# ESP32_PCB.net
KiCad netlist of a schematic drawn in Altium Designer
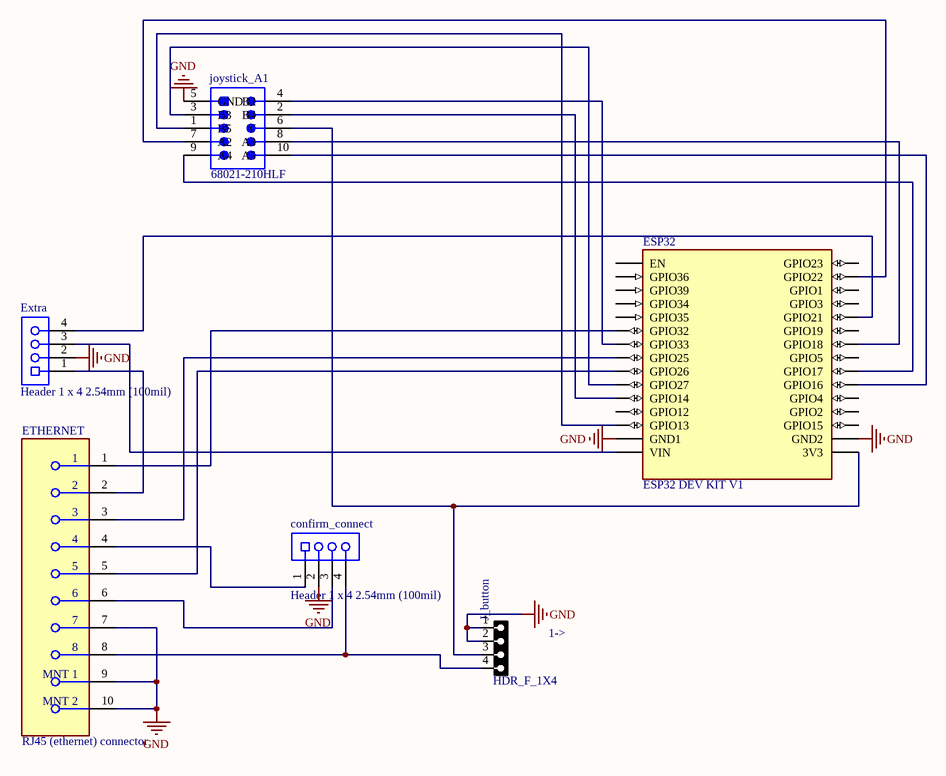
[diagram p0: ESP32_PCB.SchDoc]

(export (version "E")
  (design (tool "Eeschema 10.0.6"))
  (components
    (comp (ref "confirm_connect")
      (value "Header 1 x 4 2.54mm (100mil)")
      (footprint "New footprint 1")
      (libsource (lib "Reykjavik University") (part "New symbol 1"))
    )
    (comp (ref "ESP32")
      (value "ESP32 DEV KIT V1")
      (footprint "ESP32-DEV-KIT-V1")
      (description "ESP-WROOM-32 https://www.aliexpress.com/item/1005006771532302.html")
      (fields (field (name "MP") "ESP-WROOM-32") (field (name "MF") "Espressif Systems"))
      (libsource (lib "Reykjavik University") (part "ESP-WROOM-32"))
    )
    (comp (ref "ETHERNET")
      (value "RJ45 (ethernet) connector")
      (footprint "FP-1-406541-1-MFG")
      (description "Modular Connector, RJ45 Jack, 1 x 1 (Port), 8P8C, Cat5, Through Hole Mount")
      (libsource (lib "Reykjavik University") (part "d6c685936813e271102b42d67b1ef4a"))
    )
    (comp (ref "Extra")
      (value "Header 1 x 4 2.54mm (100mil)")
      (footprint "New footprint 1")
      (libsource (lib "") (part "New symbol 1_1"))
    )
    (comp (ref "joystick_A1")
      (value "68021-210HLF")
      (footprint "FCI-68021-210HLF-10_V")
      (description "Male Header, Pitch 2.54 mm, 2 x 5 Position, Height 4.83 mm, Tail Length 3.05 mm, Bulk")
      (fields (field (name "MANUFACTURER") "FCI Electronics"))
      (libsource (lib "Reykjavik University") (part "CN-2P-M-R10"))
    )
    (comp (ref "J_button")
      (value "HDR_F_1X4")
      (footprint "HDR_F_1X4")
      (description "Female header 1x4 2.54mm pitch")
      (libsource (lib "Reykjavik University") (part "HDRLP_F_1X4"))
    )
  )
  (nets
    (net (code "1") (name "GND") (class "Default")
      (node (ref "ESP32") (pin "J1_14") (pinfunction "GND1_J1_14") (pintype "power_in"))
      (node (ref "ESP32") (pin "J3_14") (pinfunction "GND2_J3_14") (pintype "power_in"))
      (node (ref "ETHERNET") (pin "10") (pinfunction "MNT_2_10") (pintype "passive"))
      (node (ref "ETHERNET") (pin "7") (pinfunction "7_7") (pintype "passive"))
      (node (ref "ETHERNET") (pin "9") (pinfunction "MNT_1_9") (pintype "passive"))
      (node (ref "Extra") (pin "2") (pinfunction "2_2") (pintype "passive"))
      (node (ref "J_button") (pin "1") (pinfunction "1_1") (pintype "passive"))
      (node (ref "J_button") (pin "2") (pinfunction "2_2") (pintype "passive"))
      (node (ref "confirm_connect") (pin "2") (pinfunction "2_2") (pintype "passive"))
      (node (ref "joystick_A1") (pin "5") (pinfunction "GND_5") (pintype "passive"))
    )
    (net (code "2") (name "Net-(ESP32-3V3)") (class "Default")
      (node (ref "ESP32") (pin "J3_15") (pinfunction "3V3_J3_15") (pintype "power_in"))
      (node (ref "J_button") (pin "3") (pinfunction "3_3") (pintype "passive"))
      (node (ref "joystick_A1") (pin "6") (pinfunction "V_6") (pintype "passive"))
    )
    (net (code "3") (name "Net-(ESP32-GPIO13)") (class "Default")
      (node (ref "ESP32") (pin "J1_13") (pinfunction "GPIO13_J1_13") (pintype "bidirectional"))
      (node (ref "joystick_A1") (pin "1") (pinfunction "B5_1") (pintype "passive"))
    )
    (net (code "4") (name "Net-(ESP32-GPIO14)") (class "Default")
      (node (ref "ESP32") (pin "J1_11") (pinfunction "GPIO14_J1_11") (pintype "bidirectional"))
      (node (ref "joystick_A1") (pin "2") (pinfunction "B4_2") (pintype "passive"))
    )
    (net (code "5") (name "Net-(ESP32-GPIO16)") (class "Default")
      (node (ref "ESP32") (pin "J3_10") (pinfunction "GPIO16_J3_10") (pintype "bidirectional"))
      (node (ref "joystick_A1") (pin "10") (pinfunction "A5_10") (pintype "passive"))
    )
    (net (code "6") (name "Net-(ESP32-GPIO17)") (class "Default")
      (node (ref "ESP32") (pin "J3_9") (pinfunction "GPIO17_J3_9") (pintype "bidirectional"))
      (node (ref "joystick_A1") (pin "9") (pinfunction "A4_9") (pintype "passive"))
    )
    (net (code "7") (name "Net-(ESP32-GPIO18)") (class "Default")
      (node (ref "ESP32") (pin "J3_7") (pinfunction "GPIO18_J3_7") (pintype "bidirectional"))
      (node (ref "joystick_A1") (pin "8") (pinfunction "A3_8") (pintype "passive"))
    )
    (net (code "8") (name "Net-(ESP32-GPIO21)") (class "Default")
      (node (ref "ESP32") (pin "J3_5") (pinfunction "GPIO21_J3_5") (pintype "bidirectional"))
      (node (ref "Extra") (pin "4") (pinfunction "4_4") (pintype "passive"))
    )
    (net (code "9") (name "Net-(ESP32-GPIO22)") (class "Default")
      (node (ref "ESP32") (pin "J3_2") (pinfunction "GPIO22_J3_2") (pintype "bidirectional"))
      (node (ref "joystick_A1") (pin "7") (pinfunction "A2_7") (pintype "passive"))
    )
    (net (code "10") (name "Net-(ESP32-GPIO25)") (class "Default")
      (node (ref "ESP32") (pin "J1_8") (pinfunction "GPIO25_J1_8") (pintype "bidirectional"))
      (node (ref "ETHERNET") (pin "3") (pinfunction "3_3") (pintype "passive"))
    )
    (net (code "11") (name "Net-(ESP32-GPIO26)") (class "Default")
      (node (ref "ESP32") (pin "J1_9") (pinfunction "GPIO26_J1_9") (pintype "bidirectional"))
      (node (ref "ETHERNET") (pin "5") (pinfunction "5_5") (pintype "passive"))
    )
    (net (code "12") (name "Net-(ESP32-GPIO27)") (class "Default")
      (node (ref "ESP32") (pin "J1_10") (pinfunction "GPIO27_J1_10") (pintype "bidirectional"))
      (node (ref "joystick_A1") (pin "3") (pinfunction "B3_3") (pintype "passive"))
    )
    (net (code "13") (name "Net-(ESP32-GPIO32)") (class "Default")
      (node (ref "ESP32") (pin "J1_6") (pinfunction "GPIO32_J1_6") (pintype "bidirectional"))
      (node (ref "ETHERNET") (pin "1") (pinfunction "1_1") (pintype "passive"))
    )
    (net (code "14") (name "Net-(ESP32-GPIO33)") (class "Default")
      (node (ref "ESP32") (pin "J1_7") (pinfunction "GPIO33_J1_7") (pintype "bidirectional"))
      (node (ref "joystick_A1") (pin "4") (pinfunction "B2_4") (pintype "passive"))
    )
    (net (code "15") (name "Net-(ESP32-VIN)") (class "Default")
      (node (ref "ESP32") (pin "J1_15") (pinfunction "VIN_J1_15") (pintype "power_in"))
      (node (ref "Extra") (pin "3") (pinfunction "3_3") (pintype "passive"))
    )
    (net (code "16") (name "Net-(ETHERNET-Pad2)") (class "Default")
      (node (ref "ETHERNET") (pin "2") (pinfunction "2_2") (pintype "passive"))
      (node (ref "Extra") (pin "1") (pinfunction "1_1") (pintype "passive"))
    )
    (net (code "17") (name "Net-(ETHERNET-Pad4)") (class "Default")
      (node (ref "ETHERNET") (pin "4") (pinfunction "4_4") (pintype "passive"))
      (node (ref "confirm_connect") (pin "1") (pinfunction "1_1") (pintype "passive"))
    )
    (net (code "18") (name "Net-(ETHERNET-Pad6)") (class "Default")
      (node (ref "ETHERNET") (pin "6") (pinfunction "6_6") (pintype "passive"))
      (node (ref "confirm_connect") (pin "3") (pinfunction "3_3") (pintype "passive"))
    )
    (net (code "19") (name "Net-(ETHERNET-Pad8)") (class "Default")
      (node (ref "ETHERNET") (pin "8") (pinfunction "8_8") (pintype "passive"))
      (node (ref "J_button") (pin "4") (pinfunction "4_4") (pintype "passive"))
      (node (ref "confirm_connect") (pin "4") (pinfunction "4_4") (pintype "passive"))
    )
    (net (code "20") (name "unconnected-(ESP32-EN-PadJ1_1)") (class "Default")
      (node (ref "ESP32") (pin "J1_1") (pinfunction "EN_J1_1") (pintype "power_in"))
    )
    (net (code "21") (name "unconnected-(ESP32-GPIO1-PadJ3_3)") (class "Default")
      (node (ref "ESP32") (pin "J3_3") (pinfunction "GPIO1_J3_3") (pintype "bidirectional"))
    )
    (net (code "22") (name "unconnected-(ESP32-GPIO2-PadJ3_12)") (class "Default")
      (node (ref "ESP32") (pin "J3_12") (pinfunction "GPIO2_J3_12") (pintype "bidirectional"))
    )
    (net (code "23") (name "unconnected-(ESP32-GPIO3-PadJ3_4)") (class "Default")
      (node (ref "ESP32") (pin "J3_4") (pinfunction "GPIO3_J3_4") (pintype "bidirectional"))
    )
    (net (code "24") (name "unconnected-(ESP32-GPIO4-PadJ3_11)") (class "Default")
      (node (ref "ESP32") (pin "J3_11") (pinfunction "GPIO4_J3_11") (pintype "bidirectional"))
    )
    (net (code "25") (name "unconnected-(ESP32-GPIO5-PadJ3_8)") (class "Default")
      (node (ref "ESP32") (pin "J3_8") (pinfunction "GPIO5_J3_8") (pintype "bidirectional"))
    )
    (net (code "26") (name "unconnected-(ESP32-GPIO12-PadJ1_12)") (class "Default")
      (node (ref "ESP32") (pin "J1_12") (pinfunction "GPIO12_J1_12") (pintype "bidirectional"))
    )
    (net (code "27") (name "unconnected-(ESP32-GPIO15-PadJ3_13)") (class "Default")
      (node (ref "ESP32") (pin "J3_13") (pinfunction "GPIO15_J3_13") (pintype "bidirectional"))
    )
    (net (code "28") (name "unconnected-(ESP32-GPIO19-PadJ3_6)") (class "Default")
      (node (ref "ESP32") (pin "J3_6") (pinfunction "GPIO19_J3_6") (pintype "bidirectional"))
    )
    (net (code "29") (name "unconnected-(ESP32-GPIO23-PadJ3_1)") (class "Default")
      (node (ref "ESP32") (pin "J3_1") (pinfunction "GPIO23_J3_1") (pintype "bidirectional"))
    )
    (net (code "30") (name "unconnected-(ESP32-GPIO34-PadJ1_4)") (class "Default")
      (node (ref "ESP32") (pin "J1_4") (pinfunction "GPIO34_J1_4") (pintype "input"))
    )
    (net (code "31") (name "unconnected-(ESP32-GPIO35-PadJ1_5)") (class "Default")
      (node (ref "ESP32") (pin "J1_5") (pinfunction "GPIO35_J1_5") (pintype "input"))
    )
    (net (code "32") (name "unconnected-(ESP32-GPIO36-PadJ1_2)") (class "Default")
      (node (ref "ESP32") (pin "J1_2") (pinfunction "GPIO36_J1_2") (pintype "input"))
    )
    (net (code "33") (name "unconnected-(ESP32-GPIO39-PadJ1_3)") (class "Default")
      (node (ref "ESP32") (pin "J1_3") (pinfunction "GPIO39_J1_3") (pintype "input"))
    )
  )
)
